# controller_relays.net
KiCad netlist of a schematic drawn in EAGLE
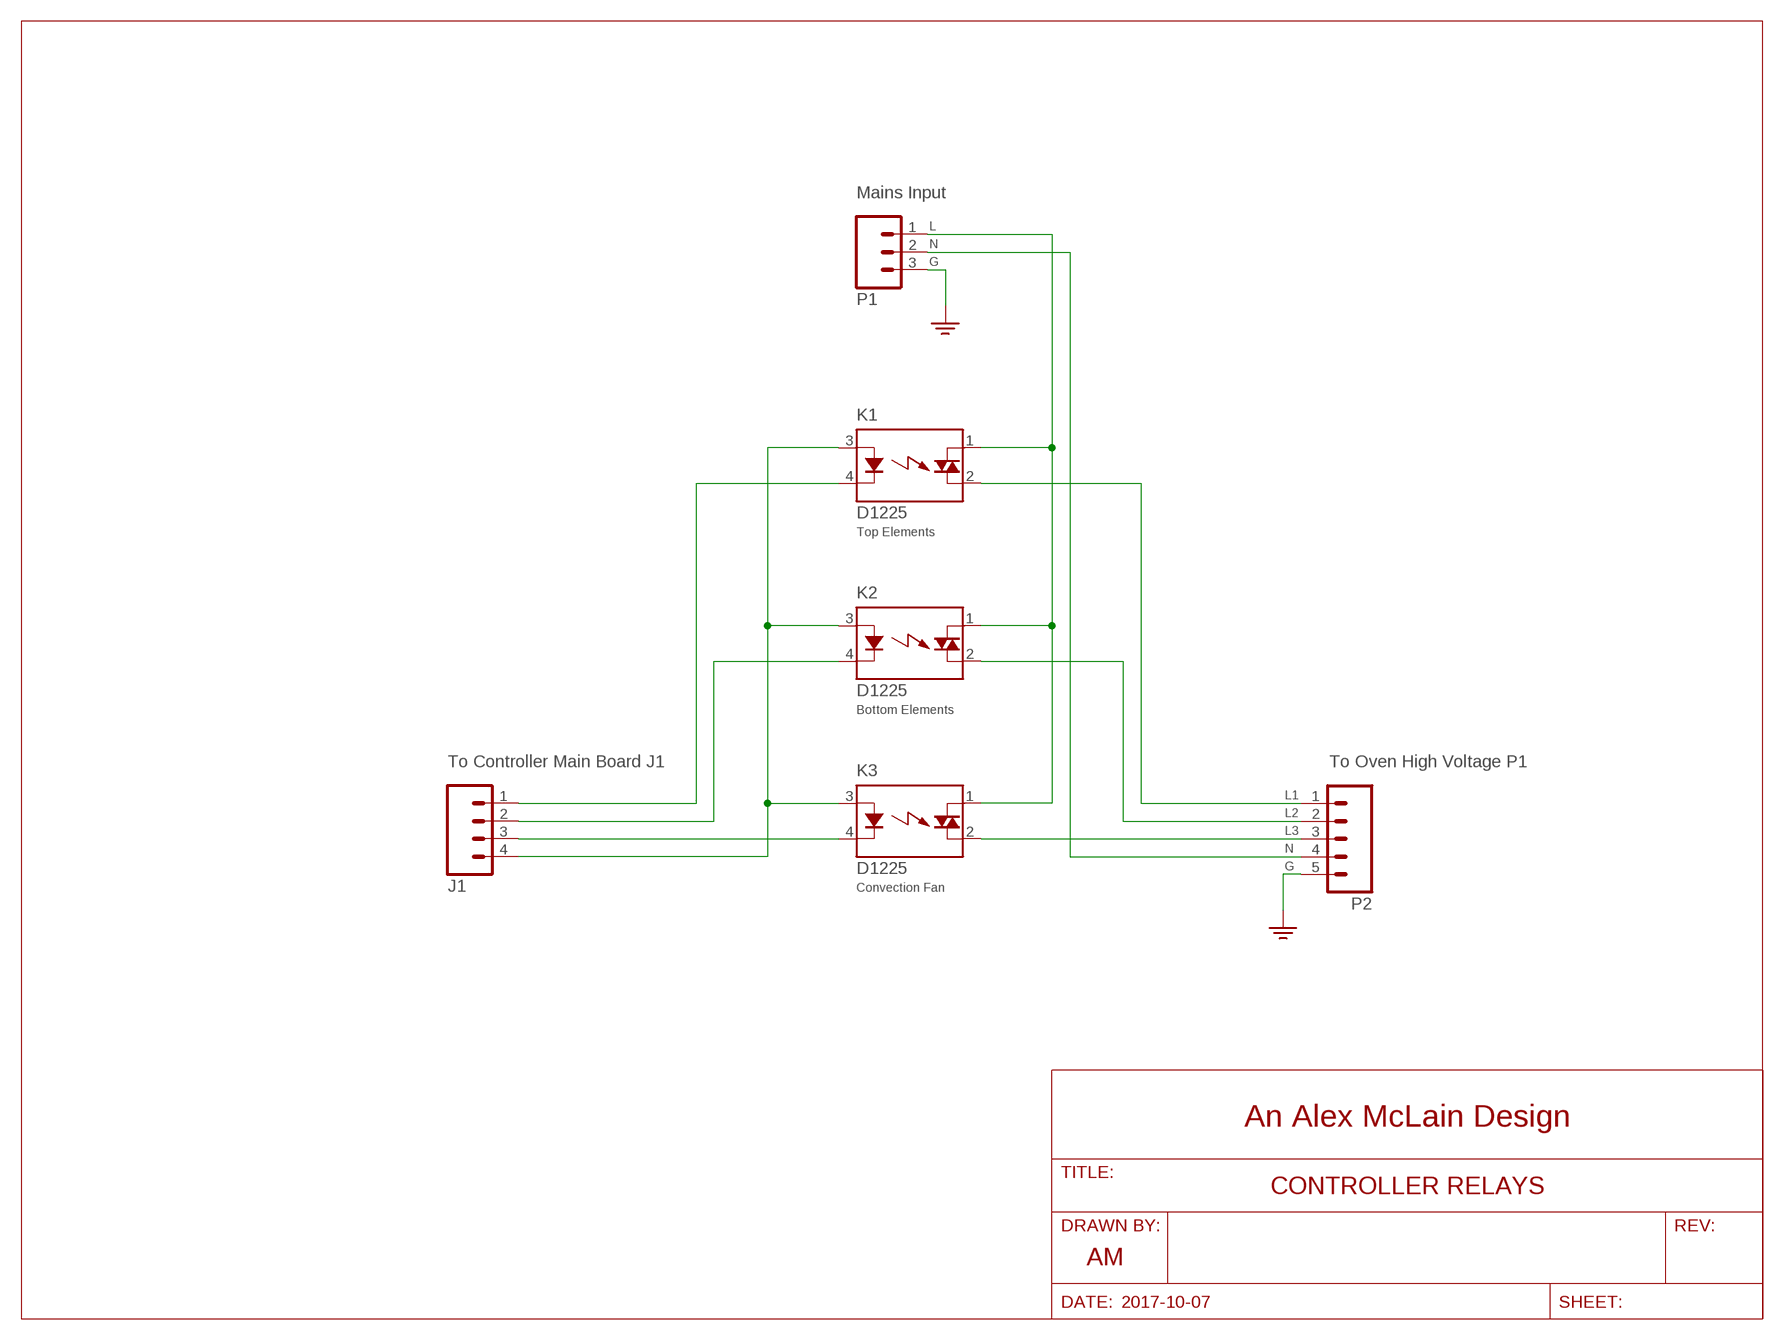
[diagram p0: schematic, sheet 1]

(export (version "E")
  (design (tool "Eeschema 10.0.6"))
  (components
    (comp (ref "J1")
      (value "MA04")
      (footprint "eagle-import:04PA")
      (libsource (lib "eagle-import") (part "MA04"))
    )
    (comp (ref "K1")
      (value "D1225")
      (footprint "eagle-import:AQ1-FLAT")
      (fields (field (name "MPN") "AQ2A2-ZP3/28VDC"))
      (libsource (lib "eagle-import") (part "AQ?2A2-J-ZP3"))
    )
    (comp (ref "K2")
      (value "D1225")
      (footprint "eagle-import:AQ1-FLAT")
      (fields (field (name "MPN") "AQ2A2-ZP3/28VDC"))
      (libsource (lib "eagle-import") (part "AQ?2A2-J-ZP3"))
    )
    (comp (ref "K3")
      (value "D1225")
      (footprint "eagle-import:AQ1-FLAT")
      (fields (field (name "MPN") "AQ2A2-ZP3/28VDC"))
      (libsource (lib "eagle-import") (part "AQ?2A2-J-ZP3"))
    )
    (comp (ref "P1")
      (value "MA03")
      (footprint "eagle-import:03P")
      (libsource (lib "eagle-import") (part "MA03"))
    )
    (comp (ref "P2")
      (value "MA05")
      (footprint "eagle-import:05PA")
      (libsource (lib "eagle-import") (part "MA05"))
    )
  )
  (nets
    (net (code "1") (name "EGND") (class "Default")
      (node (ref "P1") (pin "3") (pinfunction "3_3") (pintype "passive"))
      (node (ref "P2") (pin "5") (pinfunction "5_5") (pintype "passive"))
    )
    (net (code "2") (name "Net-(K1-A)") (class "Default")
      (node (ref "J1") (pin "4") (pinfunction "4_4") (pintype "passive"))
      (node (ref "K1") (pin "3") (pinfunction "A_3") (pintype "passive"))
      (node (ref "K2") (pin "3") (pinfunction "A_3") (pintype "passive"))
      (node (ref "K3") (pin "3") (pinfunction "A_3") (pintype "passive"))
    )
    (net (code "3") (name "Net-(K1-DS1)") (class "Default")
      (node (ref "K1") (pin "1") (pinfunction "DS1_1") (pintype "passive"))
      (node (ref "K2") (pin "1") (pinfunction "DS1_1") (pintype "passive"))
      (node (ref "K3") (pin "1") (pinfunction "DS1_1") (pintype "passive"))
      (node (ref "P1") (pin "1") (pinfunction "1_1") (pintype "passive"))
    )
    (net (code "4") (name "Net-(K1-DS2)") (class "Default")
      (node (ref "K1") (pin "2") (pinfunction "DS2_2") (pintype "passive"))
      (node (ref "P2") (pin "1") (pinfunction "1_1") (pintype "passive"))
    )
    (net (code "5") (name "Net-(K1-K)") (class "Default")
      (node (ref "J1") (pin "1") (pinfunction "1_1") (pintype "passive"))
      (node (ref "K1") (pin "4") (pinfunction "K_4") (pintype "passive"))
    )
    (net (code "6") (name "Net-(K2-DS2)") (class "Default")
      (node (ref "K2") (pin "2") (pinfunction "DS2_2") (pintype "passive"))
      (node (ref "P2") (pin "2") (pinfunction "2_2") (pintype "passive"))
    )
    (net (code "7") (name "Net-(K2-K)") (class "Default")
      (node (ref "J1") (pin "2") (pinfunction "2_2") (pintype "passive"))
      (node (ref "K2") (pin "4") (pinfunction "K_4") (pintype "passive"))
    )
    (net (code "8") (name "Net-(K3-DS2)") (class "Default")
      (node (ref "K3") (pin "2") (pinfunction "DS2_2") (pintype "passive"))
      (node (ref "P2") (pin "3") (pinfunction "3_3") (pintype "passive"))
    )
    (net (code "9") (name "Net-(K3-K)") (class "Default")
      (node (ref "J1") (pin "3") (pinfunction "3_3") (pintype "passive"))
      (node (ref "K3") (pin "4") (pinfunction "K_4") (pintype "passive"))
    )
    (net (code "10") (name "Net-(P1-Pad2)") (class "Default")
      (node (ref "P1") (pin "2") (pinfunction "2_2") (pintype "passive"))
      (node (ref "P2") (pin "4") (pinfunction "4_4") (pintype "passive"))
    )
  )
)
